# MCU.net
KiCad netlist of a schematic drawn in Altium Designer
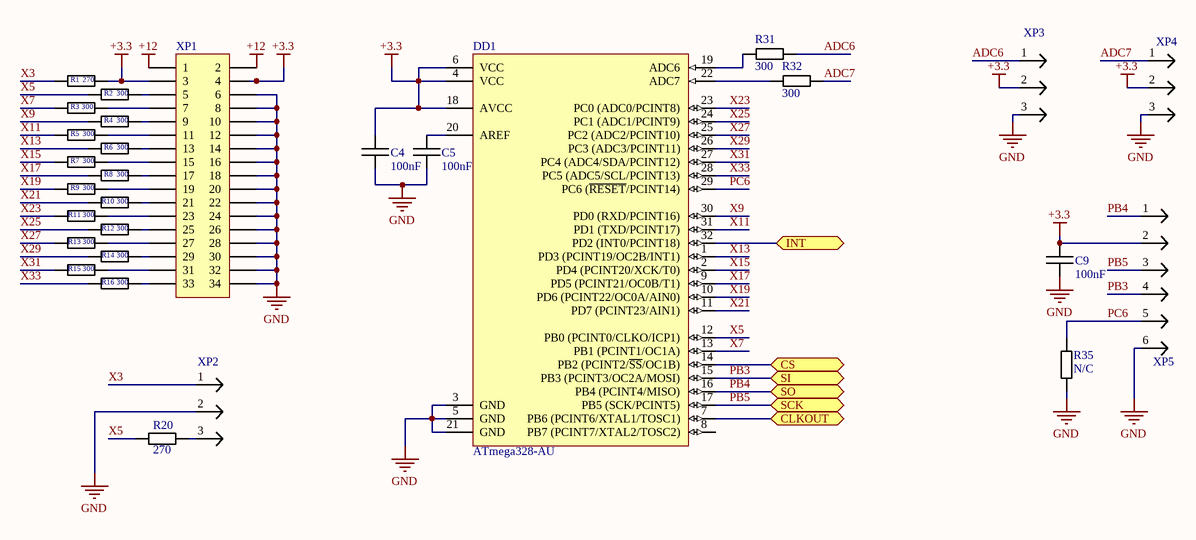
[diagram p0: MCU.SchDoc]

(export (version "E")
  (design (tool "Eeschema 10.0.6"))
  (components
    (comp (ref "C4")
      (value "CAP_SMD")
      (footprint "CAPC1206(3216)170_L")
      (description "Ceramic capacitor, 0805")
      (fields (field (name "VAL") "100nF"))
      (libsource (lib "altium-import") (part "root_1_CAP_SMD_"))
    )
    (comp (ref "C5")
      (value "CAP_SMD")
      (footprint "CAPC1206(3216)170_L")
      (description "Ceramic capacitor, 0805")
      (fields (field (name "VAL") "100nF"))
      (libsource (lib "altium-import") (part "root_1_CAP_SMD_"))
    )
    (comp (ref "C9")
      (value "CAP_SMD")
      (footprint "CAPC1206(3216)170_L")
      (description "Ceramic capacitor, 0805")
      (fields (field (name "VAL") "100nF"))
      (libsource (lib "altium-import") (part "root_1_CAP_SMD_"))
    )
    (comp (ref "DD1")
      (value "ATmega328-AU")
      (footprint "32A_L")
      (libsource (lib "altium-import") (part "root_0_ATmega328-AU_"))
    )
    (comp (ref "R1")
      (value "RES_SMD")
      (footprint "RESC1206(3216)_L")
      (description "RES0805")
      (fields (field (name "VAL") "270"))
      (libsource (lib "altium-import") (part "root_0_RES_SMD_"))
    )
    (comp (ref "R2")
      (value "RES_SMD")
      (footprint "RESC1206(3216)_L")
      (description "RES0805")
      (fields (field (name "VAL") "300"))
      (libsource (lib "altium-import") (part "root_0_RES_SMD_"))
    )
    (comp (ref "R3")
      (value "RES_SMD")
      (footprint "RESC1206(3216)_L")
      (description "RES0805")
      (fields (field (name "VAL") "300"))
      (libsource (lib "altium-import") (part "root_0_RES_SMD_"))
    )
    (comp (ref "R4")
      (value "RES_SMD")
      (footprint "RESC1206(3216)_L")
      (description "RES0805")
      (fields (field (name "VAL") "300"))
      (libsource (lib "altium-import") (part "root_0_RES_SMD_"))
    )
    (comp (ref "R5")
      (value "RES_SMD")
      (footprint "RESC1206(3216)_L")
      (description "RES0805")
      (fields (field (name "VAL") "300"))
      (libsource (lib "altium-import") (part "root_0_RES_SMD_"))
    )
    (comp (ref "R6")
      (value "RES_SMD")
      (footprint "RESC1206(3216)_L")
      (description "RES0805")
      (fields (field (name "VAL") "300"))
      (libsource (lib "altium-import") (part "root_0_RES_SMD_"))
    )
    (comp (ref "R7")
      (value "RES_SMD")
      (footprint "RESC1206(3216)_L")
      (description "RES0805")
      (fields (field (name "VAL") "300"))
      (libsource (lib "altium-import") (part "root_0_RES_SMD_"))
    )
    (comp (ref "R8")
      (value "RES_SMD")
      (footprint "RESC1206(3216)_L")
      (description "RES0805")
      (fields (field (name "VAL") "300"))
      (libsource (lib "altium-import") (part "root_0_RES_SMD_"))
    )
    (comp (ref "R9")
      (value "RES_SMD")
      (footprint "RESC1206(3216)_L")
      (description "RES0805")
      (fields (field (name "VAL") "300"))
      (libsource (lib "altium-import") (part "root_0_RES_SMD_"))
    )
    (comp (ref "R10")
      (value "RES_SMD")
      (footprint "RESC1206(3216)_L")
      (description "RES0805")
      (fields (field (name "VAL") "300"))
      (libsource (lib "altium-import") (part "root_0_RES_SMD_"))
    )
    (comp (ref "R11")
      (value "RES_SMD")
      (footprint "RESC1206(3216)_L")
      (description "RES0805")
      (fields (field (name "VAL") "300"))
      (libsource (lib "altium-import") (part "root_0_RES_SMD_"))
    )
    (comp (ref "R12")
      (value "RES_SMD")
      (footprint "RESC1206(3216)_L")
      (description "RES0805")
      (fields (field (name "VAL") "300"))
      (libsource (lib "altium-import") (part "root_0_RES_SMD_"))
    )
    (comp (ref "R13")
      (value "RES_SMD")
      (footprint "RESC1206(3216)_L")
      (description "RES0805")
      (fields (field (name "VAL") "300"))
      (libsource (lib "altium-import") (part "root_0_RES_SMD_"))
    )
    (comp (ref "R14")
      (value "RES_SMD")
      (footprint "RESC1206(3216)_L")
      (description "RES0805")
      (fields (field (name "VAL") "300"))
      (libsource (lib "altium-import") (part "root_0_RES_SMD_"))
    )
    (comp (ref "R15")
      (value "RES_SMD")
      (footprint "RESC1206(3216)_L")
      (description "RES0805")
      (fields (field (name "VAL") "300"))
      (libsource (lib "altium-import") (part "root_0_RES_SMD_"))
    )
    (comp (ref "R16")
      (value "RES_SMD")
      (footprint "RESC1206(3216)_L")
      (description "RES0805")
      (fields (field (name "VAL") "300"))
      (libsource (lib "altium-import") (part "root_0_RES_SMD_"))
    )
    (comp (ref "R20")
      (value "RES_SMD")
      (footprint "RESC1206(3216)_L")
      (description "RES0805")
      (fields (field (name "VAL") "270"))
      (libsource (lib "altium-import") (part "root_0_RES_SMD_"))
    )
    (comp (ref "R31")
      (value "RES_SMD")
      (footprint "RESC1206(3216)_L")
      (description "RES0805")
      (fields (field (name "VAL") "300"))
      (libsource (lib "altium-import") (part "root_0_RES_SMD_"))
    )
    (comp (ref "R32")
      (value "RES_SMD")
      (footprint "RESC1206(3216)_L")
      (description "RES0805")
      (fields (field (name "VAL") "300"))
      (libsource (lib "altium-import") (part "root_0_RES_SMD_"))
    )
    (comp (ref "R35")
      (value "RES_SMD")
      (footprint "RESC1206(3216)_L")
      (description "RES0805")
      (fields (field (name "VAL") "N/C"))
      (libsource (lib "altium-import") (part "root_1_RES_SMD_"))
    )
    (comp (ref "XP1")
      (value "~")
      (footprint "HDR2X17")
      (description "Header, 17-Pin, Dual row")
      (fields (field (name "PUBLISHER") "Altium Limited"))
      (libsource (lib "web.skorpio") (part "Header 17X2"))
    )
    (comp (ref "XP2")
      (value "PBS-03")
      (footprint "PBS-03")
      (libsource (lib "altium-import") (part "root_0_PBS-03_"))
    )
    (comp (ref "XP3")
      (value "PLS-03")
      (footprint "PLS-03")
      (libsource (lib "altium-import") (part "root_0_PLS-03_"))
    )
    (comp (ref "XP4")
      (value "PLS-03")
      (footprint "PLS-03")
      (libsource (lib "altium-import") (part "root_0_PLS-03_"))
    )
    (comp (ref "XP5")
      (value "PLS-03_2")
      (footprint "PLS-03_2")
      (libsource (lib "altium-import") (part "root_0_PLS-03_2_"))
    )
  )
  (nets
    (net (code "1") (name "+3.3") (class "Default")
      (node (ref "C4") (pin "2") (pinfunction "2_2") (pintype "passive"))
      (node (ref "C9") (pin "2") (pinfunction "2_2") (pintype "passive"))
      (node (ref "DD1") (pin "18") (pinfunction "AVCC_18") (pintype "power_in"))
      (node (ref "DD1") (pin "4") (pinfunction "VCC_4") (pintype "power_in"))
      (node (ref "DD1") (pin "6") (pinfunction "VCC_6") (pintype "power_in"))
      (node (ref "R1") (pin "2") (pinfunction "2_2") (pintype "passive"))
      (node (ref "XP1") (pin "3") (pinfunction "3_3") (pintype "passive"))
      (node (ref "XP1") (pin "4") (pinfunction "4_4") (pintype "passive"))
      (node (ref "XP3") (pin "2") (pinfunction "2_2") (pintype "passive"))
      (node (ref "XP4") (pin "2") (pinfunction "2_2") (pintype "passive"))
      (node (ref "XP5") (pin "2") (pinfunction "2_2") (pintype "passive"))
    )
    (net (code "2") (name "+12") (class "Default")
      (node (ref "XP1") (pin "1") (pinfunction "1_1") (pintype "passive"))
      (node (ref "XP1") (pin "2") (pinfunction "2_2") (pintype "passive"))
    )
    (net (code "3") (name "/ADC6") (class "Default")
      (node (ref "R31") (pin "2") (pinfunction "2_2") (pintype "passive"))
      (node (ref "XP3") (pin "1") (pinfunction "1_1") (pintype "passive"))
    )
    (net (code "4") (name "/ADC7") (class "Default")
      (node (ref "R32") (pin "2") (pinfunction "2_2") (pintype "passive"))
      (node (ref "XP4") (pin "1") (pinfunction "1_1") (pintype "passive"))
    )
    (net (code "5") (name "/CLKOUT") (class "Default")
      (node (ref "DD1") (pin "7") (pinfunction "PB6_(PCINT6/XTAL1/TOSC1)_7") (pintype "bidirectional"))
    )
    (net (code "6") (name "/CS") (class "Default")
      (node (ref "DD1") (pin "14") (pinfunction "PB2_(PCINT2/~{SS}/OC1B)_14") (pintype "bidirectional"))
    )
    (net (code "7") (name "/INT") (class "Default")
      (node (ref "DD1") (pin "32") (pinfunction "PD2_(INT0/PCINT18)_32") (pintype "bidirectional"))
    )
    (net (code "8") (name "/PB3") (class "Default")
      (node (ref "DD1") (pin "15") (pinfunction "PB3_(PCINT3/OC2A/MOSI)_15") (pintype "bidirectional"))
      (node (ref "XP5") (pin "4") (pinfunction "4_4") (pintype "passive"))
    )
    (net (code "9") (name "/PB4") (class "Default")
      (node (ref "DD1") (pin "16") (pinfunction "PB4_(PCINT4/MISO)_16") (pintype "bidirectional"))
      (node (ref "XP5") (pin "1") (pinfunction "1_1") (pintype "passive"))
    )
    (net (code "10") (name "/PB5") (class "Default")
      (node (ref "DD1") (pin "17") (pinfunction "PB5_(SCK/PCINT5)_17") (pintype "bidirectional"))
      (node (ref "XP5") (pin "3") (pinfunction "3_3") (pintype "passive"))
    )
    (net (code "11") (name "/PC6") (class "Default")
      (node (ref "DD1") (pin "29") (pinfunction "PC6_(~{RESET}/PCINT14)_29") (pintype "bidirectional"))
      (node (ref "R35") (pin "2") (pinfunction "2_2") (pintype "passive"))
      (node (ref "XP5") (pin "5") (pinfunction "5_5") (pintype "passive"))
    )
    (net (code "12") (name "/X3") (class "Default")
      (node (ref "R1") (pin "1") (pinfunction "1_1") (pintype "passive"))
      (node (ref "XP2") (pin "1") (pinfunction "1_1") (pintype "passive"))
    )
    (net (code "13") (name "/X5") (class "Default")
      (node (ref "DD1") (pin "12") (pinfunction "PB0_(PCINT0/CLKO/ICP1)_12") (pintype "bidirectional"))
      (node (ref "R2") (pin "1") (pinfunction "1_1") (pintype "passive"))
      (node (ref "R20") (pin "1") (pinfunction "1_1") (pintype "passive"))
    )
    (net (code "14") (name "/X7") (class "Default")
      (node (ref "DD1") (pin "13") (pinfunction "PB1_(PCINT1/OC1A)_13") (pintype "bidirectional"))
      (node (ref "R3") (pin "1") (pinfunction "1_1") (pintype "passive"))
    )
    (net (code "15") (name "/X9") (class "Default")
      (node (ref "DD1") (pin "30") (pinfunction "PD0_(RXD/PCINT16)_30") (pintype "bidirectional"))
      (node (ref "R4") (pin "1") (pinfunction "1_1") (pintype "passive"))
    )
    (net (code "16") (name "/X11") (class "Default")
      (node (ref "DD1") (pin "31") (pinfunction "PD1_(TXD/PCINT17)_31") (pintype "bidirectional"))
      (node (ref "R5") (pin "1") (pinfunction "1_1") (pintype "passive"))
    )
    (net (code "17") (name "/X13") (class "Default")
      (node (ref "DD1") (pin "1") (pinfunction "PD3_(PCINT19/OC2B/INT1)_1") (pintype "bidirectional"))
      (node (ref "R6") (pin "1") (pinfunction "1_1") (pintype "passive"))
    )
    (net (code "18") (name "/X15") (class "Default")
      (node (ref "DD1") (pin "2") (pinfunction "PD4_(PCINT20/XCK/T0)_2") (pintype "bidirectional"))
      (node (ref "R7") (pin "1") (pinfunction "1_1") (pintype "passive"))
    )
    (net (code "19") (name "/X17") (class "Default")
      (node (ref "DD1") (pin "9") (pinfunction "PD5_(PCINT21/OC0B/T1)_9") (pintype "bidirectional"))
      (node (ref "R8") (pin "1") (pinfunction "1_1") (pintype "passive"))
    )
    (net (code "20") (name "/X19") (class "Default")
      (node (ref "DD1") (pin "10") (pinfunction "PD6_(PCINT22/OC0A/AIN0)_10") (pintype "bidirectional"))
      (node (ref "R9") (pin "1") (pinfunction "1_1") (pintype "passive"))
    )
    (net (code "21") (name "/X21") (class "Default")
      (node (ref "DD1") (pin "11") (pinfunction "PD7_(PCINT23/AIN1)_11") (pintype "bidirectional"))
      (node (ref "R10") (pin "1") (pinfunction "1_1") (pintype "passive"))
    )
    (net (code "22") (name "/X23") (class "Default")
      (node (ref "DD1") (pin "23") (pinfunction "PC0_(ADC0/PCINT8)_23") (pintype "bidirectional"))
      (node (ref "R11") (pin "1") (pinfunction "1_1") (pintype "passive"))
    )
    (net (code "23") (name "/X25") (class "Default")
      (node (ref "DD1") (pin "24") (pinfunction "PC1_(ADC1/PCINT9)_24") (pintype "bidirectional"))
      (node (ref "R12") (pin "1") (pinfunction "1_1") (pintype "passive"))
    )
    (net (code "24") (name "/X27") (class "Default")
      (node (ref "DD1") (pin "25") (pinfunction "PC2_(ADC2/PCINT10)_25") (pintype "bidirectional"))
      (node (ref "R13") (pin "1") (pinfunction "1_1") (pintype "passive"))
    )
    (net (code "25") (name "/X29") (class "Default")
      (node (ref "DD1") (pin "26") (pinfunction "PC3_(ADC3/PCINT11)_26") (pintype "bidirectional"))
      (node (ref "R14") (pin "1") (pinfunction "1_1") (pintype "passive"))
    )
    (net (code "26") (name "/X31") (class "Default")
      (node (ref "DD1") (pin "27") (pinfunction "PC4_(ADC4/SDA/PCINT12)_27") (pintype "bidirectional"))
      (node (ref "R15") (pin "1") (pinfunction "1_1") (pintype "passive"))
    )
    (net (code "27") (name "/X33") (class "Default")
      (node (ref "DD1") (pin "28") (pinfunction "PC5_(ADC5/SCL/PCINT13)_28") (pintype "bidirectional"))
      (node (ref "R16") (pin "1") (pinfunction "1_1") (pintype "passive"))
    )
    (net (code "28") (name "GND") (class "Default")
      (node (ref "C4") (pin "1") (pinfunction "1_1") (pintype "passive"))
      (node (ref "C5") (pin "1") (pinfunction "1_1") (pintype "passive"))
      (node (ref "C9") (pin "1") (pinfunction "1_1") (pintype "passive"))
      (node (ref "DD1") (pin "21") (pinfunction "GND_21") (pintype "power_in"))
      (node (ref "DD1") (pin "3") (pinfunction "GND_3") (pintype "power_in"))
      (node (ref "DD1") (pin "5") (pinfunction "GND_5") (pintype "power_in"))
      (node (ref "R35") (pin "1") (pinfunction "1_1") (pintype "passive"))
      (node (ref "XP1") (pin "10") (pinfunction "10_10") (pintype "passive"))
      (node (ref "XP1") (pin "12") (pinfunction "12_12") (pintype "passive"))
      (node (ref "XP1") (pin "14") (pinfunction "14_14") (pintype "passive"))
      (node (ref "XP1") (pin "16") (pinfunction "16_16") (pintype "passive"))
      (node (ref "XP1") (pin "18") (pinfunction "18_18") (pintype "passive"))
      (node (ref "XP1") (pin "20") (pinfunction "20_20") (pintype "passive"))
      (node (ref "XP1") (pin "22") (pinfunction "22_22") (pintype "passive"))
      (node (ref "XP1") (pin "24") (pinfunction "24_24") (pintype "passive"))
      (node (ref "XP1") (pin "26") (pinfunction "26_26") (pintype "passive"))
      (node (ref "XP1") (pin "28") (pinfunction "28_28") (pintype "passive"))
      (node (ref "XP1") (pin "30") (pinfunction "30_30") (pintype "passive"))
      (node (ref "XP1") (pin "32") (pinfunction "32_32") (pintype "passive"))
      (node (ref "XP1") (pin "34") (pinfunction "34_34") (pintype "passive"))
      (node (ref "XP1") (pin "6") (pinfunction "6_6") (pintype "passive"))
      (node (ref "XP1") (pin "8") (pinfunction "8_8") (pintype "passive"))
      (node (ref "XP2") (pin "2") (pinfunction "2_2") (pintype "passive"))
      (node (ref "XP3") (pin "3") (pinfunction "3_3") (pintype "passive"))
      (node (ref "XP4") (pin "3") (pinfunction "3_3") (pintype "passive"))
      (node (ref "XP5") (pin "6") (pinfunction "6_6") (pintype "passive"))
    )
    (net (code "29") (name "Net-(DD1-ADC6)") (class "Default")
      (node (ref "DD1") (pin "19") (pinfunction "ADC6_19") (pintype "input"))
      (node (ref "R31") (pin "1") (pinfunction "1_1") (pintype "passive"))
    )
    (net (code "30") (name "Net-(DD1-ADC7)") (class "Default")
      (node (ref "DD1") (pin "22") (pinfunction "ADC7_22") (pintype "input"))
      (node (ref "R32") (pin "1") (pinfunction "1_1") (pintype "passive"))
    )
    (net (code "31") (name "Net-(DD1-AREF)") (class "Default")
      (node (ref "C5") (pin "2") (pinfunction "2_2") (pintype "passive"))
      (node (ref "DD1") (pin "20") (pinfunction "AREF_20") (pintype "passive"))
    )
    (net (code "32") (name "Net-(R2-Pad2)") (class "Default")
      (node (ref "R2") (pin "2") (pinfunction "2_2") (pintype "passive"))
      (node (ref "XP1") (pin "5") (pinfunction "5_5") (pintype "passive"))
    )
    (net (code "33") (name "Net-(R3-Pad2)") (class "Default")
      (node (ref "R3") (pin "2") (pinfunction "2_2") (pintype "passive"))
      (node (ref "XP1") (pin "7") (pinfunction "7_7") (pintype "passive"))
    )
    (net (code "34") (name "Net-(R4-Pad2)") (class "Default")
      (node (ref "R4") (pin "2") (pinfunction "2_2") (pintype "passive"))
      (node (ref "XP1") (pin "9") (pinfunction "9_9") (pintype "passive"))
    )
    (net (code "35") (name "Net-(R5-Pad2)") (class "Default")
      (node (ref "R5") (pin "2") (pinfunction "2_2") (pintype "passive"))
      (node (ref "XP1") (pin "11") (pinfunction "11_11") (pintype "passive"))
    )
    (net (code "36") (name "Net-(R6-Pad2)") (class "Default")
      (node (ref "R6") (pin "2") (pinfunction "2_2") (pintype "passive"))
      (node (ref "XP1") (pin "13") (pinfunction "13_13") (pintype "passive"))
    )
    (net (code "37") (name "Net-(R7-Pad2)") (class "Default")
      (node (ref "R7") (pin "2") (pinfunction "2_2") (pintype "passive"))
      (node (ref "XP1") (pin "15") (pinfunction "15_15") (pintype "passive"))
    )
    (net (code "38") (name "Net-(R8-Pad2)") (class "Default")
      (node (ref "R8") (pin "2") (pinfunction "2_2") (pintype "passive"))
      (node (ref "XP1") (pin "17") (pinfunction "17_17") (pintype "passive"))
    )
    (net (code "39") (name "Net-(R9-Pad2)") (class "Default")
      (node (ref "R9") (pin "2") (pinfunction "2_2") (pintype "passive"))
      (node (ref "XP1") (pin "19") (pinfunction "19_19") (pintype "passive"))
    )
    (net (code "40") (name "Net-(R10-Pad2)") (class "Default")
      (node (ref "R10") (pin "2") (pinfunction "2_2") (pintype "passive"))
      (node (ref "XP1") (pin "21") (pinfunction "21_21") (pintype "passive"))
    )
    (net (code "41") (name "Net-(R11-Pad2)") (class "Default")
      (node (ref "R11") (pin "2") (pinfunction "2_2") (pintype "passive"))
      (node (ref "XP1") (pin "23") (pinfunction "23_23") (pintype "passive"))
    )
    (net (code "42") (name "Net-(R12-Pad2)") (class "Default")
      (node (ref "R12") (pin "2") (pinfunction "2_2") (pintype "passive"))
      (node (ref "XP1") (pin "25") (pinfunction "25_25") (pintype "passive"))
    )
    (net (code "43") (name "Net-(R13-Pad2)") (class "Default")
      (node (ref "R13") (pin "2") (pinfunction "2_2") (pintype "passive"))
      (node (ref "XP1") (pin "27") (pinfunction "27_27") (pintype "passive"))
    )
    (net (code "44") (name "Net-(R14-Pad2)") (class "Default")
      (node (ref "R14") (pin "2") (pinfunction "2_2") (pintype "passive"))
      (node (ref "XP1") (pin "29") (pinfunction "29_29") (pintype "passive"))
    )
    (net (code "45") (name "Net-(R15-Pad2)") (class "Default")
      (node (ref "R15") (pin "2") (pinfunction "2_2") (pintype "passive"))
      (node (ref "XP1") (pin "31") (pinfunction "31_31") (pintype "passive"))
    )
    (net (code "46") (name "Net-(R16-Pad2)") (class "Default")
      (node (ref "R16") (pin "2") (pinfunction "2_2") (pintype "passive"))
      (node (ref "XP1") (pin "33") (pinfunction "33_33") (pintype "passive"))
    )
    (net (code "47") (name "Net-(R20-Pad2)") (class "Default")
      (node (ref "R20") (pin "2") (pinfunction "2_2") (pintype "passive"))
      (node (ref "XP2") (pin "3") (pinfunction "3_3") (pintype "passive"))
    )
    (net (code "48") (name "unconnected-(DD1-PB7_(PCINT7{slash}XTAL2{slash}TOSC2)-Pad8)") (class "Default")
      (node (ref "DD1") (pin "8") (pinfunction "PB7_(PCINT7/XTAL2/TOSC2)_8") (pintype "bidirectional"))
    )
  )
)
